# BMS-MCU_old.net
KiCad netlist of a schematic drawn in Altium Designer
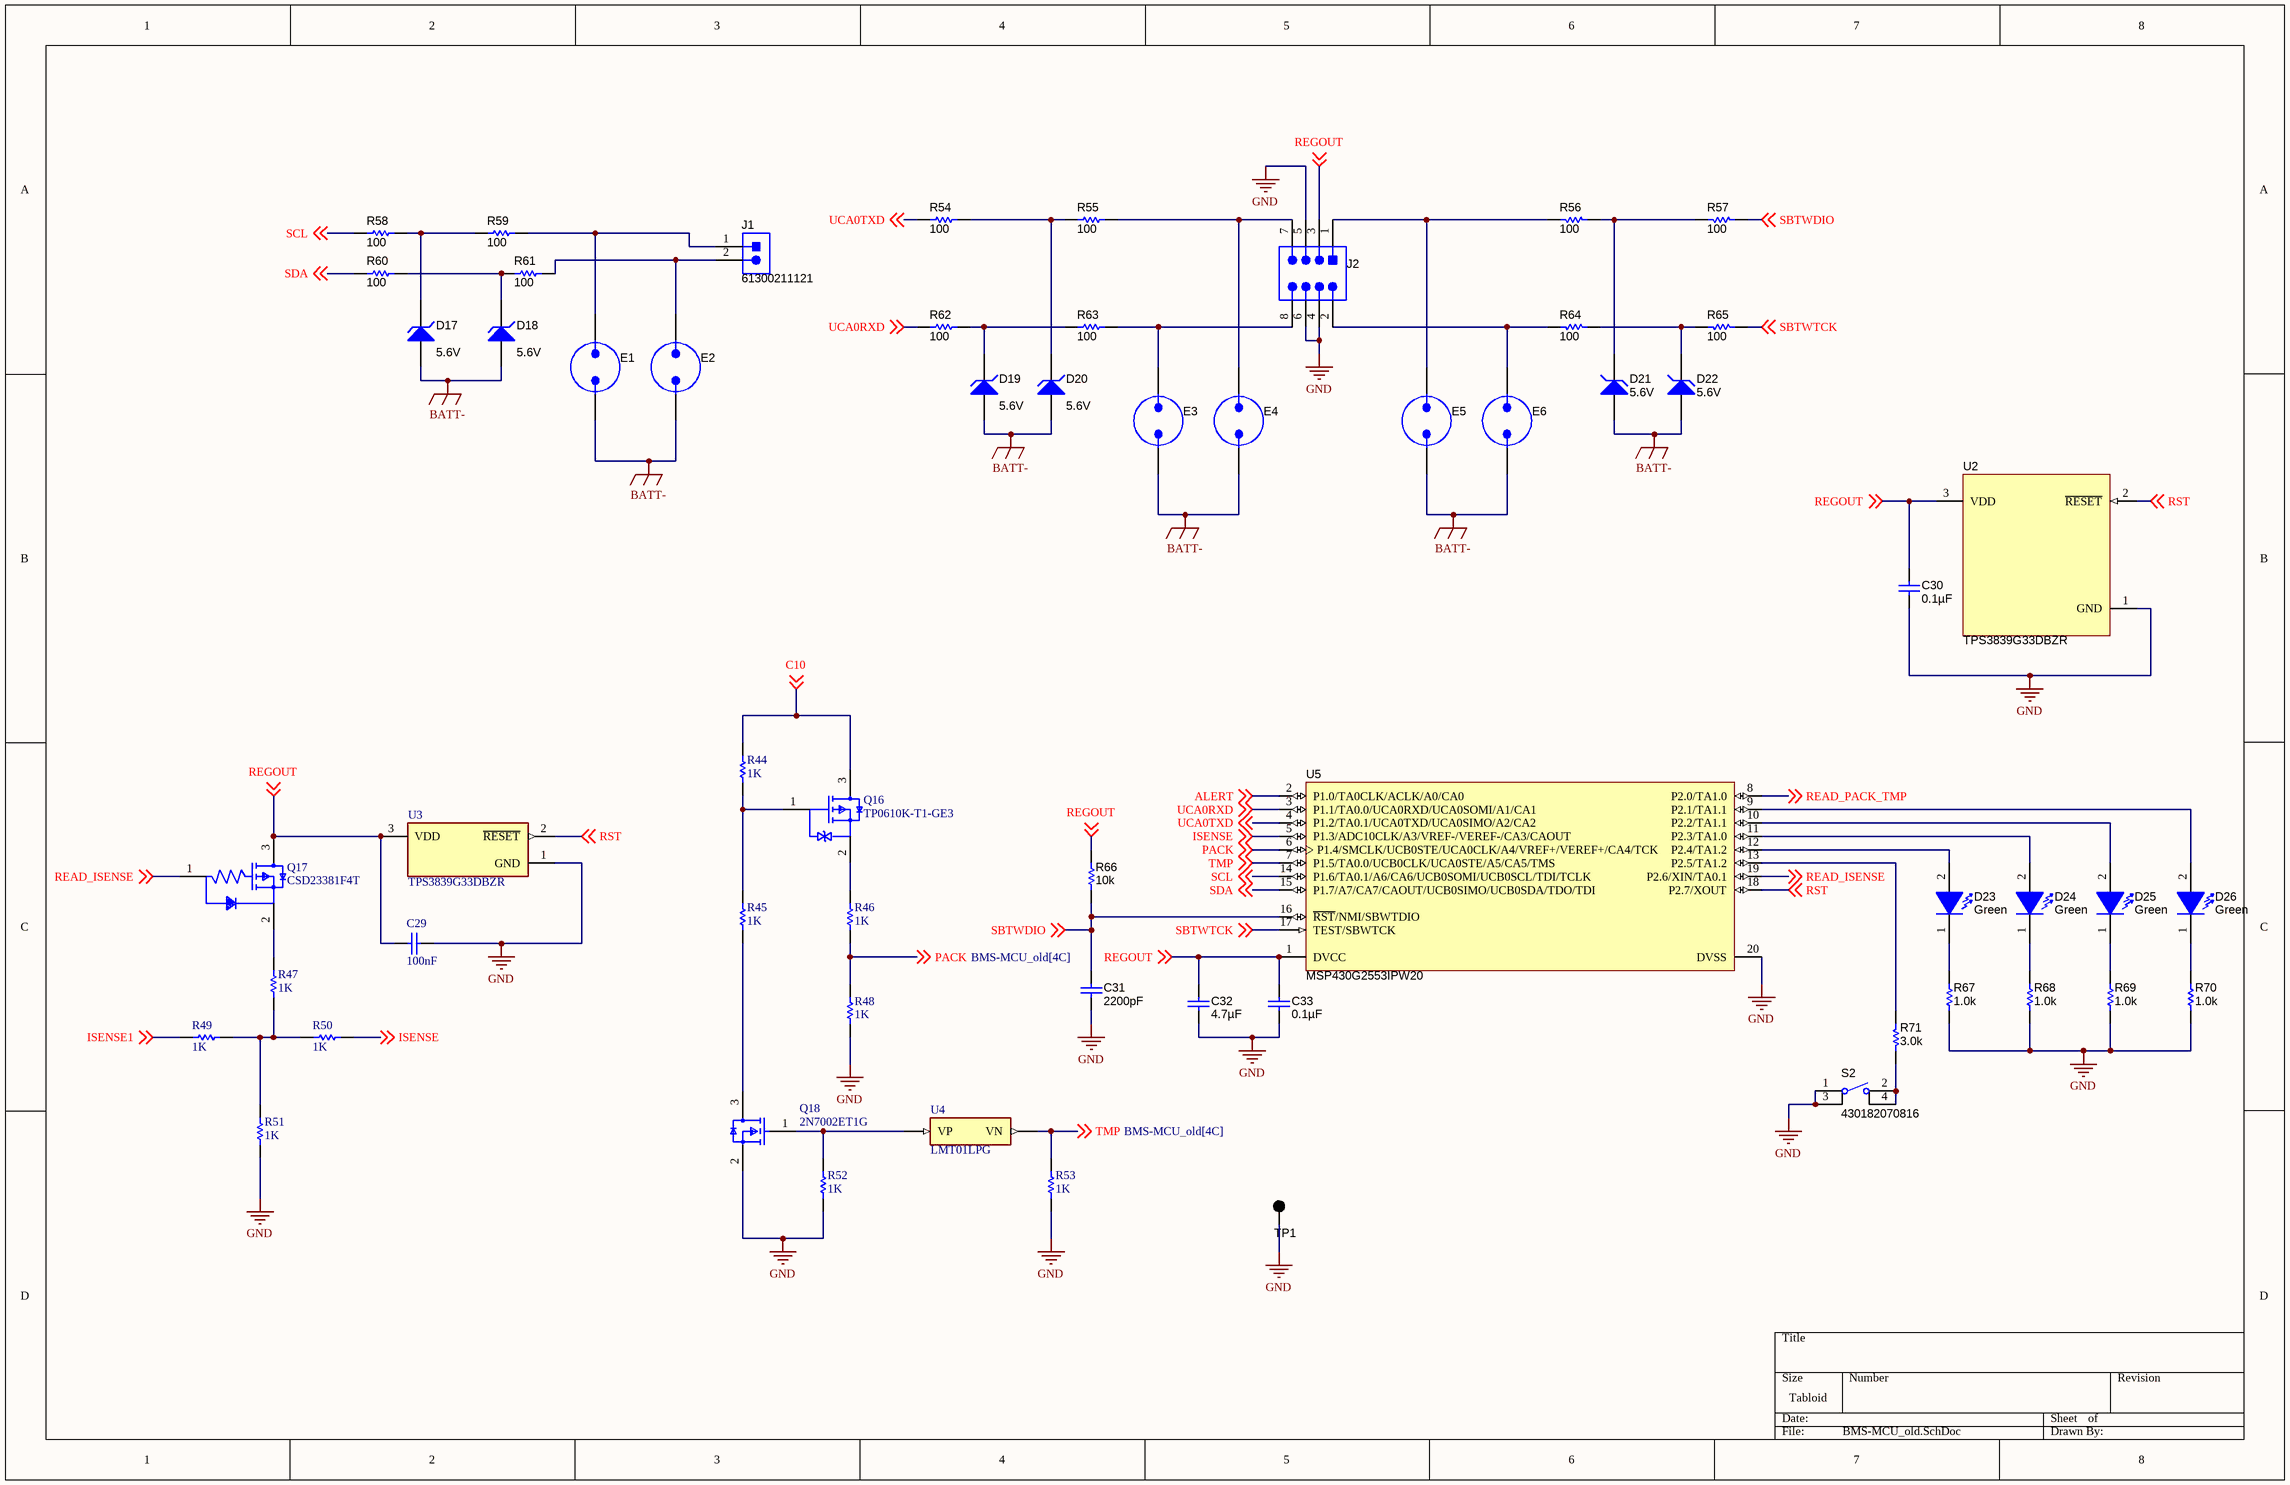
[diagram p0: BMS-MCU_old.SchDoc]

(export (version "E")
  (design (tool "Eeschema 10.0.6"))
  (components
    (comp (ref "C29")
      (value "885012206046")
      (footprint "WCAP-CSGP_0603_L1.6W0.8H0.8_Reflow")
      (fields (field (name "TOLERANCE") "10%") (field (name "CAPACITANCE") "100nF"))
      (libsource (lib "BMS-lib") (part "CMP-03913-53914755-1"))
    )
    (comp (ref "C30")
      (value "885012206046")
      (footprint "0603_095")
      (description "CAP, CERM, 0.1 µF, 16 V, +/- 10%, X7R, 0603_095")
      (fields
        (field (name "VALUEDISPLAYED") "0.1µF")
        (field (name "MANUFACTURER") "Wurth Elektronik")
        (field (name "PUBLISHER") "Texas Instruments")
      )
      (libsource (lib "Capacitor_Ceramic") (part "885012206046"))
    )
    (comp (ref "C31")
      (value "885012206036")
      (footprint "0603_095")
      (description "CAP, CERM, 2200 pF, 16 V, +/- 10%, X7R, 0603_095")
      (fields
        (field (name "VALUEDISPLAYED") "2200pF")
        (field (name "MANUFACTURER") "Wurth Elektronik")
        (field (name "PUBLISHER") "Texas Instruments")
      )
      (libsource (lib "Capacitor_Ceramic") (part "885012206036"))
    )
    (comp (ref "C32")
      (value "885012207025")
      (footprint "0805_145")
      (description "CAP, CERM, 4.7 µF, 10 V, +/- 10%, X7R, 0805")
      (fields
        (field (name "VALUEDISPLAYED") "4.7µF")
        (field (name "MANUFACTURER") "Wurth Elektronik")
        (field (name "PUBLISHER") "Texas Instruments")
      )
      (libsource (lib "Capacitor_Ceramic") (part "885012207025"))
    )
    (comp (ref "C33")
      (value "885012206046")
      (footprint "0603_095")
      (description "CAP, CERM, 0.1 µF, 16 V, +/- 10%, X7R, 0603_095")
      (fields
        (field (name "VALUEDISPLAYED") "0.1µF")
        (field (name "MANUFACTURER") "Wurth Elektronik")
        (field (name "PUBLISHER") "Texas Instruments")
      )
      (libsource (lib "Capacitor_Ceramic") (part "885012206046"))
    )
    (comp (ref "D17")
      (value "5.6V")
      (footprint "sod-323")
      (description "Diode, Zener, 5.6V, 200mW, SOD-323")
      (fields
        (field (name "PARTNUMBER") "MMSZ5232BS-7-F")
        (field (name "MANUFACTURER") "Diodes Inc.")
        (field (name "PUBLISHER") "Texas Instruments")
      )
      (libsource (lib "ZenerDiodes") (part "MMSZ5232BS-7-F"))
    )
    (comp (ref "D18")
      (value "5.6V")
      (footprint "sod-323")
      (description "Diode, Zener, 5.6V, 200mW, SOD-323")
      (fields
        (field (name "PARTNUMBER") "MMSZ5232BS-7-F")
        (field (name "MANUFACTURER") "Diodes Inc.")
        (field (name "PUBLISHER") "Texas Instruments")
      )
      (libsource (lib "ZenerDiodes") (part "MMSZ5232BS-7-F"))
    )
    (comp (ref "D19")
      (value "5.6V")
      (footprint "sod-323")
      (description "Diode, Zener, 5.6V, 200mW, SOD-323")
      (fields
        (field (name "PARTNUMBER") "MMSZ5232BS-7-F")
        (field (name "MANUFACTURER") "Diodes Inc.")
        (field (name "PUBLISHER") "Texas Instruments")
      )
      (libsource (lib "ZenerDiodes") (part "MMSZ5232BS-7-F"))
    )
    (comp (ref "D20")
      (value "5.6V")
      (footprint "sod-323")
      (description "Diode, Zener, 5.6V, 200mW, SOD-323")
      (fields
        (field (name "PARTNUMBER") "MMSZ5232BS-7-F")
        (field (name "MANUFACTURER") "Diodes Inc.")
        (field (name "PUBLISHER") "Texas Instruments")
      )
      (libsource (lib "ZenerDiodes") (part "MMSZ5232BS-7-F"))
    )
    (comp (ref "D21")
      (value "5.6V")
      (footprint "sod-323")
      (description "Diode, Zener, 5.6V, 200mW, SOD-323")
      (fields
        (field (name "PARTNUMBER") "MMSZ5232BS-7-F")
        (field (name "MANUFACTURER") "Diodes Inc.")
        (field (name "PUBLISHER") "Texas Instruments")
      )
      (libsource (lib "ZenerDiodes") (part "MMSZ5232BS-7-F"))
    )
    (comp (ref "D22")
      (value "5.6V")
      (footprint "sod-323")
      (description "Diode, Zener, 5.6V, 200mW, SOD-323")
      (fields
        (field (name "PARTNUMBER") "MMSZ5232BS-7-F")
        (field (name "MANUFACTURER") "Diodes Inc.")
        (field (name "PUBLISHER") "Texas Instruments")
      )
      (libsource (lib "ZenerDiodes") (part "MMSZ5232BS-7-F"))
    )
    (comp (ref "D23")
      (value "Green")
      (footprint "WL-SMCW_GREEN")
      (description "LED, Green, SMD")
      (fields
        (field (name "MANUFACTURER") "Wurth Elektronik")
        (field (name "PARTNUMBER") "150060GS75000")
        (field (name "PUBLISHER") "Texas Instruments")
      )
      (libsource (lib "LED") (part "150060GS75000"))
    )
    (comp (ref "D24")
      (value "Green")
      (footprint "WL-SMCW_GREEN")
      (description "LED, Green, SMD")
      (fields
        (field (name "MANUFACTURER") "Wurth Elektronik")
        (field (name "PARTNUMBER") "150060GS75000")
        (field (name "PUBLISHER") "Texas Instruments")
      )
      (libsource (lib "LED") (part "150060GS75000"))
    )
    (comp (ref "D25")
      (value "Green")
      (footprint "WL-SMCW_GREEN")
      (description "LED, Green, SMD")
      (fields
        (field (name "MANUFACTURER") "Wurth Elektronik")
        (field (name "PARTNUMBER") "150060GS75000")
        (field (name "PUBLISHER") "Texas Instruments")
      )
      (libsource (lib "LED") (part "150060GS75000"))
    )
    (comp (ref "D26")
      (value "Green")
      (footprint "WL-SMCW_GREEN")
      (description "LED, Green, SMD")
      (fields
        (field (name "MANUFACTURER") "Wurth Elektronik")
        (field (name "PARTNUMBER") "150060GS75000")
        (field (name "PUBLISHER") "Texas Instruments")
      )
      (libsource (lib "LED") (part "150060GS75000"))
    )
    (comp (ref "E1")
      (value "N/A")
      (footprint "SPARK_GAP2")
      (description "Spark Gap")
      (fields (field (name "SYMBOLCREATOR") "a0412235") (field (name "PUBLISHER") "Texas Instruments"))
      (libsource (lib "MiscParts") (part "SparkGap"))
    )
    (comp (ref "E2")
      (value "N/A")
      (footprint "SPARK_GAP2")
      (description "Spark Gap")
      (fields (field (name "SYMBOLCREATOR") "a0412235") (field (name "PUBLISHER") "Texas Instruments"))
      (libsource (lib "MiscParts") (part "SparkGap"))
    )
    (comp (ref "E3")
      (value "N/A")
      (footprint "SPARK_GAP2")
      (description "Spark Gap")
      (fields (field (name "SYMBOLCREATOR") "a0412235") (field (name "PUBLISHER") "Texas Instruments"))
      (libsource (lib "MiscParts") (part "SparkGap"))
    )
    (comp (ref "E4")
      (value "N/A")
      (footprint "SPARK_GAP2")
      (description "Spark Gap")
      (fields (field (name "SYMBOLCREATOR") "a0412235") (field (name "PUBLISHER") "Texas Instruments"))
      (libsource (lib "MiscParts") (part "SparkGap"))
    )
    (comp (ref "E5")
      (value "N/A")
      (footprint "SPARK_GAP2")
      (description "Spark Gap")
      (fields (field (name "SYMBOLCREATOR") "a0412235") (field (name "PUBLISHER") "Texas Instruments"))
      (libsource (lib "MiscParts") (part "SparkGap"))
    )
    (comp (ref "E6")
      (value "N/A")
      (footprint "SPARK_GAP2")
      (description "Spark Gap")
      (fields (field (name "SYMBOLCREATOR") "a0412235") (field (name "PUBLISHER") "Texas Instruments"))
      (libsource (lib "MiscParts") (part "SparkGap"))
    )
    (comp (ref "J1")
      (value "61300211121")
      (footprint "WURTH_61300211121")
      (description "Header, 2.54 mm, 2x1, Gold, TH")
      (fields
        (field (name "MANUFACTURER") "Wurth Elektronik")
        (field (name "SYMBOLCREATOR") "a0412235")
        (field (name "PUBLISHER") "Texas Instruments")
      )
      (libsource (lib "Connectors_Other") (part "61300211121"))
    )
    (comp (ref "J2")
      (value "PEC04DAAN")
      (footprint "CONN_PEC04DAAN")
      (description "Header, 100mil, 4x2, Tin, TH")
      (fields
        (field (name "MANUFACTURER") "Sullins Connector Solutions")
        (field (name "SYMBOLCREATOR") "a0411947")
        (field (name "PUBLISHER") "Texas Instruments")
      )
      (libsource (lib "Connectors_Sullins") (part "PEC04DAAN"))
    )
    (comp (ref "Q16")
      (value "TP0610K-T1-GE3")
      (footprint "FP-S-03946-IPC_C")
      (description "MOSFET P-CH 60V 185MA SOT23-3")
      (libsource (lib "BMS-lib") (part "CMP-02550-000326-1"))
    )
    (comp (ref "Q17")
      (value "CSD23381F4T")
      (footprint "FP-YJC0003A-MFG")
      (description "MOSFET P-CH 12V 2.3A 3PICOSTAR")
      (libsource (lib "BMS-lib") (part "CMP-04962-000081-1"))
    )
    (comp (ref "Q18")
      (value "2N7002ET1G")
      (footprint "FP-318-08-MFG")
      (description "MOSFET N-CH 60V 260MA SOT-23")
      (libsource (lib "BMS-lib") (part "CMP-1058-00769-2"))
    )
    (comp (ref "R44")
      (value "1K")
      (description "Resistor")
      (libsource (lib "Simulation Generic Components") (part "Resistor"))
    )
    (comp (ref "R45")
      (value "1K")
      (description "Resistor")
      (libsource (lib "Simulation Generic Components") (part "Resistor"))
    )
    (comp (ref "R46")
      (value "1K")
      (description "Resistor")
      (libsource (lib "Simulation Generic Components") (part "Resistor"))
    )
    (comp (ref "R47")
      (value "1K")
      (description "Resistor")
      (libsource (lib "Simulation Generic Components") (part "Resistor"))
    )
    (comp (ref "R48")
      (value "1K")
      (description "Resistor")
      (libsource (lib "Simulation Generic Components") (part "Resistor"))
    )
    (comp (ref "R49")
      (value "1K")
      (description "Resistor")
      (libsource (lib "Simulation Generic Components") (part "Resistor"))
    )
    (comp (ref "R50")
      (value "1K")
      (description "Resistor")
      (libsource (lib "Simulation Generic Components") (part "Resistor"))
    )
    (comp (ref "R51")
      (value "1K")
      (description "Resistor")
      (libsource (lib "Simulation Generic Components") (part "Resistor"))
    )
    (comp (ref "R52")
      (value "1K")
      (description "Resistor")
      (libsource (lib "Simulation Generic Components") (part "Resistor"))
    )
    (comp (ref "R53")
      (value "1K")
      (description "Resistor")
      (libsource (lib "Simulation Generic Components") (part "Resistor"))
    )
    (comp (ref "R54")
      (value "100")
      (footprint "0805_HV")
      (description "RES, 100 ohm, 1%, 0.125W, 0805")
      (fields
        (field (name "PARTNUMBER") "CRCW0805100RFKEA")
        (field (name "MANUFACTURER") "Vishay-Dale")
        (field (name "PUBLISHER") "Texas Instruments")
      )
      (libsource (lib "Resistor_0805") (part "CRCW0805100RFKEA"))
    )
    (comp (ref "R55")
      (value "100")
      (footprint "0805_HV")
      (description "RES, 100 ohm, 1%, 0.125W, 0805")
      (fields
        (field (name "PARTNUMBER") "CRCW0805100RFKEA")
        (field (name "MANUFACTURER") "Vishay-Dale")
        (field (name "PUBLISHER") "Texas Instruments")
      )
      (libsource (lib "Resistor_0805") (part "CRCW0805100RFKEA"))
    )
    (comp (ref "R56")
      (value "100")
      (footprint "0805_HV")
      (description "RES, 100 ohm, 1%, 0.125W, 0805")
      (fields
        (field (name "PARTNUMBER") "CRCW0805100RFKEA")
        (field (name "MANUFACTURER") "Vishay-Dale")
        (field (name "PUBLISHER") "Texas Instruments")
      )
      (libsource (lib "Resistor_0805") (part "CRCW0805100RFKEA"))
    )
    (comp (ref "R57")
      (value "100")
      (footprint "0805_HV")
      (description "RES, 100 ohm, 1%, 0.125W, 0805")
      (fields
        (field (name "PARTNUMBER") "CRCW0805100RFKEA")
        (field (name "MANUFACTURER") "Vishay-Dale")
        (field (name "PUBLISHER") "Texas Instruments")
      )
      (libsource (lib "Resistor_0805") (part "CRCW0805100RFKEA"))
    )
    (comp (ref "R58")
      (value "100")
      (footprint "0805_HV")
      (description "RES, 100 ohm, 1%, 0.125W, 0805")
      (fields
        (field (name "PARTNUMBER") "CRCW0805100RFKEA")
        (field (name "MANUFACTURER") "Vishay-Dale")
        (field (name "PUBLISHER") "Texas Instruments")
      )
      (libsource (lib "Resistor_0805") (part "CRCW0805100RFKEA"))
    )
    (comp (ref "R59")
      (value "100")
      (footprint "0805_HV")
      (description "RES, 100 ohm, 1%, 0.125W, 0805")
      (fields
        (field (name "PARTNUMBER") "CRCW0805100RFKEA")
        (field (name "MANUFACTURER") "Vishay-Dale")
        (field (name "PUBLISHER") "Texas Instruments")
      )
      (libsource (lib "Resistor_0805") (part "CRCW0805100RFKEA"))
    )
    (comp (ref "R60")
      (value "100")
      (footprint "0805_HV")
      (description "RES, 100 ohm, 1%, 0.125W, 0805")
      (fields
        (field (name "PARTNUMBER") "CRCW0805100RFKEA")
        (field (name "MANUFACTURER") "Vishay-Dale")
        (field (name "PUBLISHER") "Texas Instruments")
      )
      (libsource (lib "Resistor_0805") (part "CRCW0805100RFKEA"))
    )
    (comp (ref "R61")
      (value "100")
      (footprint "0805_HV")
      (description "RES, 100 ohm, 1%, 0.125W, 0805")
      (fields
        (field (name "PARTNUMBER") "CRCW0805100RFKEA")
        (field (name "MANUFACTURER") "Vishay-Dale")
        (field (name "PUBLISHER") "Texas Instruments")
      )
      (libsource (lib "Resistor_0805") (part "CRCW0805100RFKEA"))
    )
    (comp (ref "R62")
      (value "100")
      (footprint "0805_HV")
      (description "RES, 100 ohm, 1%, 0.125W, 0805")
      (fields
        (field (name "PARTNUMBER") "CRCW0805100RFKEA")
        (field (name "MANUFACTURER") "Vishay-Dale")
        (field (name "PUBLISHER") "Texas Instruments")
      )
      (libsource (lib "Resistor_0805") (part "CRCW0805100RFKEA"))
    )
    (comp (ref "R63")
      (value "100")
      (footprint "0805_HV")
      (description "RES, 100 ohm, 1%, 0.125W, 0805")
      (fields
        (field (name "PARTNUMBER") "CRCW0805100RFKEA")
        (field (name "MANUFACTURER") "Vishay-Dale")
        (field (name "PUBLISHER") "Texas Instruments")
      )
      (libsource (lib "Resistor_0805") (part "CRCW0805100RFKEA"))
    )
    (comp (ref "R64")
      (value "100")
      (footprint "0805_HV")
      (description "RES, 100 ohm, 1%, 0.125W, 0805")
      (fields
        (field (name "PARTNUMBER") "CRCW0805100RFKEA")
        (field (name "MANUFACTURER") "Vishay-Dale")
        (field (name "PUBLISHER") "Texas Instruments")
      )
      (libsource (lib "Resistor_0805") (part "CRCW0805100RFKEA"))
    )
    (comp (ref "R65")
      (value "100")
      (footprint "0805_HV")
      (description "RES, 100 ohm, 1%, 0.125W, 0805")
      (fields
        (field (name "PARTNUMBER") "CRCW0805100RFKEA")
        (field (name "MANUFACTURER") "Vishay-Dale")
        (field (name "PUBLISHER") "Texas Instruments")
      )
      (libsource (lib "Resistor_0805") (part "CRCW0805100RFKEA"))
    )
    (comp (ref "R66")
      (value "CRCW060310K0JNEA")
      (footprint "0603")
      (description "RES, 10 k, 5%, 0.1 W, 0603")
      (fields
        (field (name "VALUEDISPLAYED") "10k")
        (field (name "MANUFACTURER") "Vishay-Dale")
        (field (name "PUBLISHER") "Texas Instruments")
      )
      (libsource (lib "Resistor_0603") (part "CRCW060310K0JNEA"))
    )
    (comp (ref "R67")
      (value "CRCW06031K00JNEA")
      (footprint "0603")
      (description "RES, 1.0 k, 5%, 0.1 W, 0603")
      (fields
        (field (name "VALUEDISPLAYED") "1.0k")
        (field (name "MANUFACTURER") "Vishay-Dale")
        (field (name "PUBLISHER") "Texas Instruments")
      )
      (libsource (lib "Resistor_0603") (part "CRCW06031K00JNEA"))
    )
    (comp (ref "R68")
      (value "CRCW06031K00JNEA")
      (footprint "0603")
      (description "RES, 1.0 k, 5%, 0.1 W, 0603")
      (fields
        (field (name "VALUEDISPLAYED") "1.0k")
        (field (name "MANUFACTURER") "Vishay-Dale")
        (field (name "PUBLISHER") "Texas Instruments")
      )
      (libsource (lib "Resistor_0603") (part "CRCW06031K00JNEA"))
    )
    (comp (ref "R69")
      (value "CRCW06031K00JNEA")
      (footprint "0603")
      (description "RES, 1.0 k, 5%, 0.1 W, 0603")
      (fields
        (field (name "VALUEDISPLAYED") "1.0k")
        (field (name "MANUFACTURER") "Vishay-Dale")
        (field (name "PUBLISHER") "Texas Instruments")
      )
      (libsource (lib "Resistor_0603") (part "CRCW06031K00JNEA"))
    )
    (comp (ref "R70")
      (value "CRCW06031K00JNEA")
      (footprint "0603")
      (description "RES, 1.0 k, 5%, 0.1 W, 0603")
      (fields
        (field (name "VALUEDISPLAYED") "1.0k")
        (field (name "MANUFACTURER") "Vishay-Dale")
        (field (name "PUBLISHER") "Texas Instruments")
      )
      (libsource (lib "Resistor_0603") (part "CRCW06031K00JNEA"))
    )
    (comp (ref "R71")
      (value "CRCW06033K00JNEA")
      (footprint "0603")
      (description "RES, 3.0 k, 5%, 0.1 W, 0603")
      (fields
        (field (name "VALUEDISPLAYED") "3.0k")
        (field (name "MANUFACTURER") "Vishay-Dale")
        (field (name "PUBLISHER") "Texas Instruments")
      )
      (libsource (lib "Resistor_0603") (part "CRCW06033K00JNEA"))
    )
    (comp (ref "S2")
      (value "430182070816")
      (footprint "SW_430182070816")
      (description "Switch, SPST-NO, Off-Mom, 1 Pos, 0.05A, 12 VDC, SMT")
      (fields
        (field (name "MANUFACTURER") "Wurth Elektronik")
        (field (name "SYMBOLCREATOR") "Altium")
        (field (name "PUBLISHER") "Texas Instruments")
      )
      (libsource (lib "Switches") (part "430182070816"))
    )
    (comp (ref "TP1")
      (value "5001")
      (footprint "Keystone5001")
      (description "Test Point, Miniature, Black, TH")
      (fields (field (name "MANUFACTURER") "Keystone") (field (name "PUBLISHER") "Texas Instruments"))
      (libsource (lib "Connectors_Keystone") (part "5001"))
    )
    (comp (ref "U2")
      (value "TPS3839G33DBZR")
      (footprint "DBZ0003A_N")
      (description "Ultralow Power, Supply Voltage Supervisor, DBZ0003A")
      (fields
        (field (name "ALTERNATE PARTNUMBER") "TPS3839G33DBZT")
        (field (name "MANUFACTURER") "Texas Instruments")
        (field (name "SYMBOLCREATOR") "Altium")
        (field (name "PUBLISHER") "Texas Instruments")
      )
      (libsource (lib "TI_Pre_Release") (part "TPS3839G33DBZR"))
    )
    (comp (ref "U3")
      (value "TPS3839G33DBZR")
      (footprint "FP-DBZ0003A-MFG")
      (description "IC SUPERVISOR 1 CHANNEL SOT23-3")
      (libsource (lib "BMS-lib") (part "CMP-04919-000025-1"))
    )
    (comp (ref "U4")
      (value "LMT01LPG")
      (footprint "FP-LPG0002A-MFG")
      (description "SENSOR DIGITAL -50C-150C TO92-2")
      (fields
        (field (name "OCTOPART") "https://octopart.com/lmt01lpg-texas+instruments-60770464")
        (field (name "MANUFACTURER") "Texas Instruments")
      )
      (libsource (lib "BMS-lib") (part "CMP-04948-000023-1"))
    )
    (comp (ref "U5")
      (value "MSP430G2553IPW20")
      (footprint "PW0020A_N")
      (fields
        (field (name "ALTERNATE PARTNUMBER") "Equivalent")
        (field (name "MANUFACTURER") "Texas Instruments")
      )
      (libsource (lib "TI MCU MSP430") (part "MSP430G2553IPW20"))
    )
  )
  (nets
    (net (code "1") (name "ALERT") (class "Default")
      (node (ref "U5") (pin "2") (pinfunction "P1.0/TA0CLK/ACLK/A0/CA0_2") (pintype "bidirectional"))
    )
    (net (code "2") (name "BATT-") (class "Default")
      (node (ref "D17") (pin "2") (pinfunction "A_2") (pintype "passive"))
      (node (ref "D18") (pin "2") (pinfunction "A_2") (pintype "passive"))
      (node (ref "D19") (pin "2") (pinfunction "A_2") (pintype "passive"))
      (node (ref "D20") (pin "2") (pinfunction "A_2") (pintype "passive"))
      (node (ref "D21") (pin "2") (pinfunction "A_2") (pintype "passive"))
      (node (ref "D22") (pin "2") (pinfunction "A_2") (pintype "passive"))
      (node (ref "E1") (pin "2") (pinfunction "2_2") (pintype "passive"))
      (node (ref "E2") (pin "2") (pinfunction "2_2") (pintype "passive"))
      (node (ref "E3") (pin "2") (pinfunction "2_2") (pintype "passive"))
      (node (ref "E4") (pin "2") (pinfunction "2_2") (pintype "passive"))
      (node (ref "E5") (pin "2") (pinfunction "2_2") (pintype "passive"))
      (node (ref "E6") (pin "2") (pinfunction "2_2") (pintype "passive"))
    )
    (net (code "3") (name "C10") (class "Default")
      (node (ref "Q16") (pin "3") (pinfunction "D_3") (pintype "passive"))
      (node (ref "R44") (pin "2") (pinfunction "2_2") (pintype "passive"))
    )
    (net (code "4") (name "GND") (class "Default")
      (node (ref "C29") (pin "2") (pinfunction "2_2") (pintype "passive"))
      (node (ref "C30") (pin "2") (pinfunction "2_2") (pintype "passive"))
      (node (ref "C31") (pin "2") (pinfunction "2_2") (pintype "passive"))
      (node (ref "C32") (pin "2") (pinfunction "2_2") (pintype "passive"))
      (node (ref "C33") (pin "2") (pinfunction "2_2") (pintype "passive"))
      (node (ref "J2") (pin "4") (pinfunction "4_4") (pintype "passive"))
      (node (ref "J2") (pin "5") (pinfunction "5_5") (pintype "passive"))
      (node (ref "J2") (pin "6") (pinfunction "6_6") (pintype "passive"))
      (node (ref "Q18") (pin "2") (pinfunction "Source_2") (pintype "passive"))
      (node (ref "R48") (pin "1") (pinfunction "1_1") (pintype "passive"))
      (node (ref "R51") (pin "1") (pinfunction "1_1") (pintype "passive"))
      (node (ref "R52") (pin "1") (pinfunction "1_1") (pintype "passive"))
      (node (ref "R53") (pin "1") (pinfunction "1_1") (pintype "passive"))
      (node (ref "R67") (pin "1") (pinfunction "1_1") (pintype "passive"))
      (node (ref "R68") (pin "1") (pinfunction "1_1") (pintype "passive"))
      (node (ref "R69") (pin "1") (pinfunction "1_1") (pintype "passive"))
      (node (ref "R70") (pin "1") (pinfunction "1_1") (pintype "passive"))
      (node (ref "S2") (pin "1") (pinfunction "1_1") (pintype "passive"))
      (node (ref "S2") (pin "3") (pinfunction "3_3") (pintype "passive"))
      (node (ref "TP1") (pin "1") (pintype "passive"))
      (node (ref "U2") (pin "1") (pinfunction "GND_1") (pintype "power_in"))
      (node (ref "U3") (pin "1") (pinfunction "GND_1") (pintype "power_in"))
      (node (ref "U5") (pin "20") (pinfunction "DVSS_20") (pintype "power_in"))
    )
    (net (code "5") (name "ISENSE") (class "Default")
      (node (ref "R50") (pin "1") (pinfunction "1_1") (pintype "passive"))
      (node (ref "U5") (pin "5") (pinfunction "P1.3/ADC10CLK/A3/VREF-/VEREF-/CA3/CAOUT_5") (pintype "bidirectional"))
    )
    (net (code "6") (name "ISENSE1") (class "Default")
      (node (ref "R49") (pin "2") (pinfunction "2_2") (pintype "passive"))
    )
    (net (code "7") (name "Net-(D17-K)") (class "Default")
      (node (ref "D17") (pin "1") (pinfunction "K_1") (pintype "passive"))
      (node (ref "R58") (pin "2") (pinfunction "2_2") (pintype "passive"))
      (node (ref "R59") (pin "1") (pinfunction "1_1") (pintype "passive"))
    )
    (net (code "8") (name "Net-(D18-K)") (class "Default")
      (node (ref "D18") (pin "1") (pinfunction "K_1") (pintype "passive"))
      (node (ref "R60") (pin "2") (pinfunction "2_2") (pintype "passive"))
      (node (ref "R61") (pin "1") (pinfunction "1_1") (pintype "passive"))
    )
    (net (code "9") (name "Net-(D19-K)") (class "Default")
      (node (ref "D19") (pin "1") (pinfunction "K_1") (pintype "passive"))
      (node (ref "R62") (pin "2") (pinfunction "2_2") (pintype "passive"))
      (node (ref "R63") (pin "1") (pinfunction "1_1") (pintype "passive"))
    )
    (net (code "10") (name "Net-(D20-K)") (class "Default")
      (node (ref "D20") (pin "1") (pinfunction "K_1") (pintype "passive"))
      (node (ref "R54") (pin "2") (pinfunction "2_2") (pintype "passive"))
      (node (ref "R55") (pin "1") (pinfunction "1_1") (pintype "passive"))
    )
    (net (code "11") (name "Net-(D21-K)") (class "Default")
      (node (ref "D21") (pin "1") (pinfunction "K_1") (pintype "passive"))
      (node (ref "R56") (pin "1") (pinfunction "1_1") (pintype "passive"))
      (node (ref "R57") (pin "2") (pinfunction "2_2") (pintype "passive"))
    )
    (net (code "12") (name "Net-(D22-K)") (class "Default")
      (node (ref "D22") (pin "1") (pinfunction "K_1") (pintype "passive"))
      (node (ref "R64") (pin "1") (pinfunction "1_1") (pintype "passive"))
      (node (ref "R65") (pin "2") (pinfunction "2_2") (pintype "passive"))
    )
    (net (code "13") (name "Net-(D23-A)") (class "Default")
      (node (ref "D23") (pin "2") (pinfunction "A_2") (pintype "passive"))
      (node (ref "U5") (pin "12") (pinfunction "P2.4/TA1.2_12") (pintype "bidirectional"))
    )
    (net (code "14") (name "Net-(D23-K)") (class "Default")
      (node (ref "D23") (pin "1") (pinfunction "K_1") (pintype "passive"))
      (node (ref "R67") (pin "2") (pinfunction "2_2") (pintype "passive"))
    )
    (net (code "15") (name "Net-(D24-A)") (class "Default")
      (node (ref "D24") (pin "2") (pinfunction "A_2") (pintype "passive"))
      (node (ref "U5") (pin "11") (pinfunction "P2.3/TA1.0_11") (pintype "bidirectional"))
    )
    (net (code "16") (name "Net-(D24-K)") (class "Default")
      (node (ref "D24") (pin "1") (pinfunction "K_1") (pintype "passive"))
      (node (ref "R68") (pin "2") (pinfunction "2_2") (pintype "passive"))
    )
    (net (code "17") (name "Net-(D25-A)") (class "Default")
      (node (ref "D25") (pin "2") (pinfunction "A_2") (pintype "passive"))
      (node (ref "U5") (pin "10") (pinfunction "P2.2/TA1.1_10") (pintype "bidirectional"))
    )
    (net (code "18") (name "Net-(D25-K)") (class "Default")
      (node (ref "D25") (pin "1") (pinfunction "K_1") (pintype "passive"))
      (node (ref "R69") (pin "2") (pinfunction "2_2") (pintype "passive"))
    )
    (net (code "19") (name "Net-(D26-A)") (class "Default")
      (node (ref "D26") (pin "2") (pinfunction "A_2") (pintype "passive"))
      (node (ref "U5") (pin "9") (pinfunction "P2.1/TA1.1_9") (pintype "bidirectional"))
    )
    (net (code "20") (name "Net-(D26-K)") (class "Default")
      (node (ref "D26") (pin "1") (pinfunction "K_1") (pintype "passive"))
      (node (ref "R70") (pin "2") (pinfunction "2_2") (pintype "passive"))
    )
    (net (code "21") (name "Net-(E1-Pad1)") (class "Default")
      (node (ref "E1") (pin "1") (pinfunction "1_1") (pintype "passive"))
      (node (ref "J1") (pin "1") (pinfunction "1_1") (pintype "passive"))
      (node (ref "R59") (pin "2") (pinfunction "2_2") (pintype "passive"))
    )
    (net (code "22") (name "Net-(E2-Pad1)") (class "Default")
      (node (ref "E2") (pin "1") (pinfunction "1_1") (pintype "passive"))
      (node (ref "J1") (pin "2") (pinfunction "2_2") (pintype "passive"))
      (node (ref "R61") (pin "2") (pinfunction "2_2") (pintype "passive"))
    )
    (net (code "23") (name "Net-(E3-Pad1)") (class "Default")
      (node (ref "E3") (pin "1") (pinfunction "1_1") (pintype "passive"))
      (node (ref "J2") (pin "8") (pinfunction "8_8") (pintype "passive"))
      (node (ref "R63") (pin "2") (pinfunction "2_2") (pintype "passive"))
    )
    (net (code "24") (name "Net-(E4-Pad1)") (class "Default")
      (node (ref "E4") (pin "1") (pinfunction "1_1") (pintype "passive"))
      (node (ref "J2") (pin "7") (pinfunction "7_7") (pintype "passive"))
      (node (ref "R55") (pin "2") (pinfunction "2_2") (pintype "passive"))
    )
    (net (code "25") (name "Net-(E5-Pad1)") (class "Default")
      (node (ref "E5") (pin "1") (pinfunction "1_1") (pintype "passive"))
      (node (ref "J2") (pin "1") (pinfunction "1_1") (pintype "passive"))
      (node (ref "R56") (pin "2") (pinfunction "2_2") (pintype "passive"))
    )
    (net (code "26") (name "Net-(E6-Pad1)") (class "Default")
      (node (ref "E6") (pin "1") (pinfunction "1_1") (pintype "passive"))
      (node (ref "J2") (pin "2") (pinfunction "2_2") (pintype "passive"))
      (node (ref "R64") (pin "2") (pinfunction "2_2") (pintype "passive"))
    )
    (net (code "27") (name "Net-(Q16-G)") (class "Default")
      (node (ref "Q16") (pin "1") (pinfunction "G_1") (pintype "passive"))
      (node (ref "R44") (pin "1") (pinfunction "1_1") (pintype "passive"))
      (node (ref "R45") (pin "2") (pinfunction "2_2") (pintype "passive"))
    )
    (net (code "28") (name "Net-(Q16-S)") (class "Default")
      (node (ref "Q16") (pin "2") (pinfunction "S_2") (pintype "passive"))
      (node (ref "R46") (pin "2") (pinfunction "2_2") (pintype "passive"))
    )
    (net (code "29") (name "Net-(Q17-S)") (class "Default")
      (node (ref "Q17") (pin "2") (pinfunction "S_2") (pintype "passive"))
      (node (ref "R47") (pin "2") (pinfunction "2_2") (pintype "passive"))
    )
    (net (code "30") (name "Net-(Q18-Drain)") (class "Default")
      (node (ref "Q18") (pin "3") (pinfunction "Drain_3") (pintype "passive"))
      (node (ref "R45") (pin "1") (pinfunction "1_1") (pintype "passive"))
    )
    (net (code "31") (name "Net-(Q18-Gate)") (class "Default")
      (node (ref "Q18") (pin "1") (pinfunction "Gate_1") (pintype "passive"))
      (node (ref "R52") (pin "2") (pinfunction "2_2") (pintype "passive"))
      (node (ref "U4") (pin "2") (pinfunction "VP_2") (pintype "input"))
    )
    (net (code "32") (name "Net-(R47-Pad1)") (class "Default")
      (node (ref "R47") (pin "1") (pinfunction "1_1") (pintype "passive"))
      (node (ref "R49") (pin "1") (pinfunction "1_1") (pintype "passive"))
      (node (ref "R50") (pin "2") (pinfunction "2_2") (pintype "passive"))
      (node (ref "R51") (pin "2") (pinfunction "2_2") (pintype "passive"))
    )
    (net (code "33") (name "Net-(R71-Pad1)") (class "Default")
      (node (ref "R71") (pin "1") (pinfunction "1_1") (pintype "passive"))
      (node (ref "S2") (pin "2") (pinfunction "2_2") (pintype "passive"))
      (node (ref "S2") (pin "4") (pinfunction "4_4") (pintype "passive"))
    )
    (net (code "34") (name "Net-(U5-P2.5{slash}TA1.2)") (class "Default")
      (node (ref "R71") (pin "2") (pinfunction "2_2") (pintype "passive"))
      (node (ref "U5") (pin "13") (pinfunction "P2.5/TA1.2_13") (pintype "bidirectional"))
    )
    (net (code "35") (name "PACK") (class "Default")
      (node (ref "R46") (pin "1") (pinfunction "1_1") (pintype "passive"))
      (node (ref "R48") (pin "2") (pinfunction "2_2") (pintype "passive"))
      (node (ref "U5") (pin "6") (pinfunction "P1.4/SMCLK/UCB0STE/UCA0CLK/A4/VREF+/VEREF+/CA4/TCK_6") (pintype "bidirectional"))
    )
    (net (code "36") (name "READ_ISENSE") (class "Default")
      (node (ref "Q17") (pin "1") (pinfunction "G_1") (pintype "passive"))
      (node (ref "U5") (pin "19") (pinfunction "P2.6/XIN/TA0.1_19") (pintype "bidirectional"))
    )
    (net (code "37") (name "READ_PACK_TMP") (class "Default")
      (node (ref "U5") (pin "8") (pinfunction "P2.0/TA1.0_8") (pintype "bidirectional"))
    )
    (net (code "38") (name "REGOUT") (class "Default")
      (node (ref "C29") (pin "1") (pinfunction "1_1") (pintype "passive"))
      (node (ref "C30") (pin "1") (pinfunction "1_1") (pintype "passive"))
      (node (ref "C32") (pin "1") (pinfunction "1_1") (pintype "passive"))
      (node (ref "C33") (pin "1") (pinfunction "1_1") (pintype "passive"))
      (node (ref "J2") (pin "3") (pinfunction "3_3") (pintype "passive"))
      (node (ref "Q17") (pin "3") (pinfunction "D_3") (pintype "passive"))
      (node (ref "R66") (pin "2") (pinfunction "2_2") (pintype "passive"))
      (node (ref "U2") (pin "3") (pinfunction "VDD_3") (pintype "power_in"))
      (node (ref "U3") (pin "3") (pinfunction "VDD_3") (pintype "power_in"))
      (node (ref "U5") (pin "1") (pinfunction "DVCC_1") (pintype "power_in"))
    )
    (net (code "39") (name "RST") (class "Default")
      (node (ref "U2") (pin "2") (pinfunction "RESET_2") (pintype "input"))
      (node (ref "U3") (pin "2") (pinfunction "~{RESET}_2") (pintype "output"))
      (node (ref "U5") (pin "18") (pinfunction "P2.7/XOUT_18") (pintype "bidirectional"))
    )
    (net (code "40") (name "SBTWDIO") (class "Default")
      (node (ref "C31") (pin "1") (pinfunction "1_1") (pintype "passive"))
      (node (ref "R57") (pin "1") (pinfunction "1_1") (pintype "passive"))
      (node (ref "R66") (pin "1") (pinfunction "1_1") (pintype "passive"))
      (node (ref "U5") (pin "16") (pinfunction "~{RST}/NMI/SBWTDIO_16") (pintype "bidirectional"))
    )
    (net (code "41") (name "SBTWTCK") (class "Default")
      (node (ref "R65") (pin "1") (pinfunction "1_1") (pintype "passive"))
      (node (ref "U5") (pin "17") (pinfunction "TEST/SBWTCK_17") (pintype "input"))
    )
    (net (code "42") (name "SCL") (class "Default")
      (node (ref "R58") (pin "1") (pinfunction "1_1") (pintype "passive"))
      (node (ref "U5") (pin "14") (pinfunction "P1.6/TA0.1/A6/CA6/UCB0SOMI/UCB0SCL/TDI/TCLK_14") (pintype "bidirectional"))
    )
    (net (code "43") (name "SDA") (class "Default")
      (node (ref "R60") (pin "1") (pinfunction "1_1") (pintype "passive"))
      (node (ref "U5") (pin "15") (pinfunction "P1.7/A7/CA7/CAOUT/UCB0SIMO/UCB0SDA/TDO/TDI_15") (pintype "bidirectional"))
    )
    (net (code "44") (name "TMP") (class "Default")
      (node (ref "R53") (pin "2") (pinfunction "2_2") (pintype "passive"))
      (node (ref "U4") (pin "1") (pinfunction "VN_1") (pintype "output"))
      (node (ref "U5") (pin "7") (pinfunction "P1.5/TA0.0/UCB0CLK/UCA0STE/A5/CA5/TMS_7") (pintype "bidirectional"))
    )
    (net (code "45") (name "UCA0RXD") (class "Default")
      (node (ref "R62") (pin "1") (pinfunction "1_1") (pintype "passive"))
      (node (ref "U5") (pin "3") (pinfunction "P1.1/TA0.0/UCA0RXD/UCA0SOMI/A1/CA1_3") (pintype "bidirectional"))
    )
    (net (code "46") (name "UCA0TXD") (class "Default")
      (node (ref "R54") (pin "1") (pinfunction "1_1") (pintype "passive"))
      (node (ref "U5") (pin "4") (pinfunction "P1.2/TA0.1/UCA0TXD/UCA0SIMO/A2/CA2_4") (pintype "bidirectional"))
    )
  )
)
